# demo2.net
KiCad netlist of a schematic drawn in EAGLE
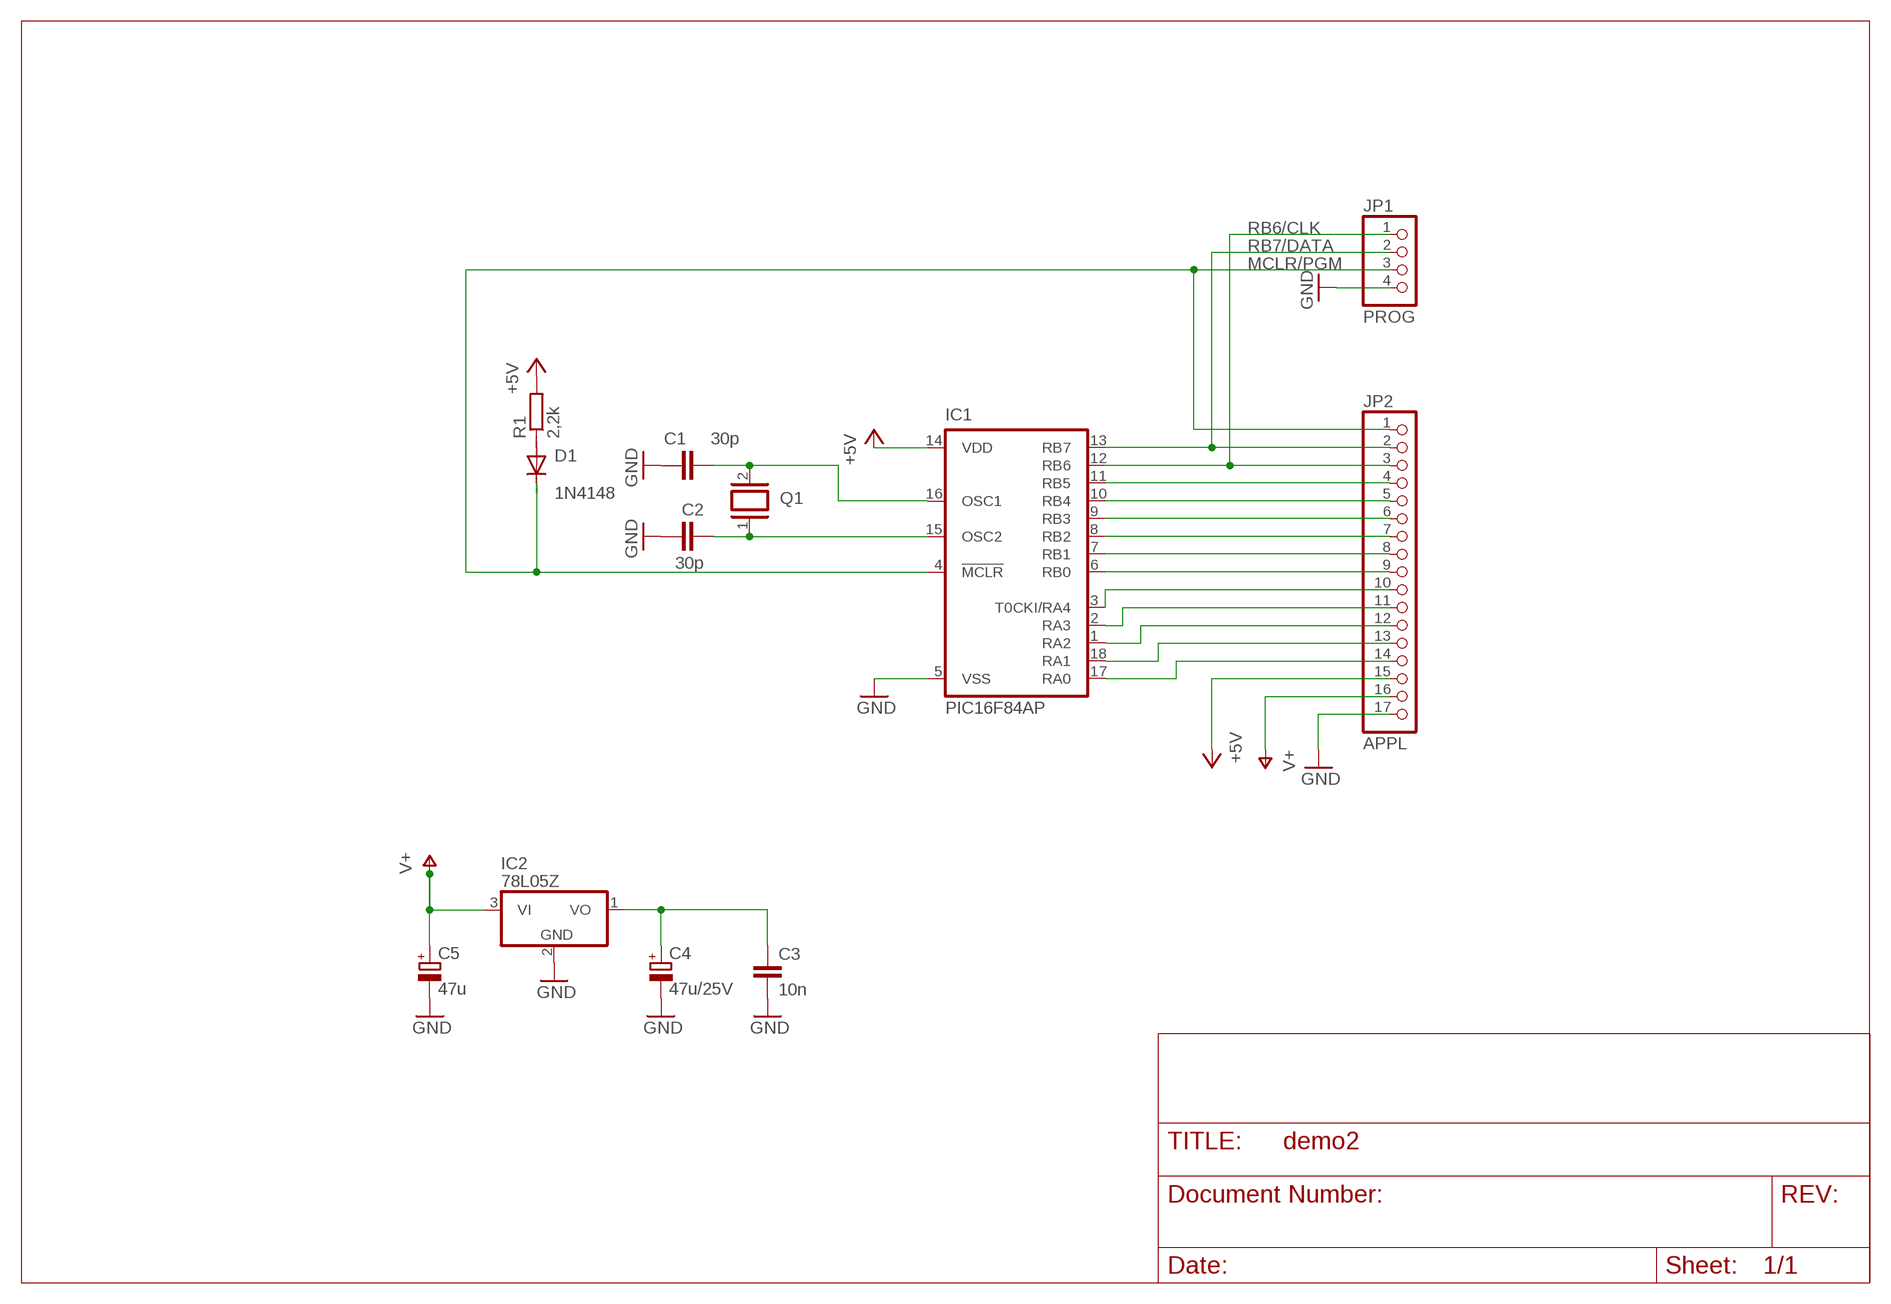
[diagram p0: schematic, sheet 1]

(export (version "E")
  (design (tool "Eeschema 10.0.6"))
  (components
    (comp (ref "C1")
      (value "30p")
      (footprint "eagle-import:C1206")
      (libsource (lib "eagle-import") (part "C-EUC1206"))
    )
    (comp (ref "C2")
      (value "30p")
      (footprint "eagle-import:C1206")
      (libsource (lib "eagle-import") (part "C-EUC1206"))
    )
    (comp (ref "C3")
      (value "10n")
      (footprint "eagle-import:C025-025X050")
      (libsource (lib "eagle-import") (part "C-EU025-025X050"))
    )
    (comp (ref "C4")
      (value "47u/25V")
      (footprint "eagle-import:TAP5-45")
      (libsource (lib "eagle-import") (part "CPOL-EUTAP5-45"))
    )
    (comp (ref "C5")
      (value "47u")
      (footprint "eagle-import:TAP5-45")
      (libsource (lib "eagle-import") (part "CPOL-EUTAP5-45"))
    )
    (comp (ref "D1")
      (value "1N4148")
      (footprint "eagle-import:DO35-10")
      (libsource (lib "eagle-import") (part "1N4148DO35-10"))
    )
    (comp (ref "IC1")
      (value "PIC16F84AP")
      (footprint "eagle-import:DIL18")
      (fields (field (name "MF") "MICROCHIP") (field (name "MPN") "PIC16F84A-04I/P"))
      (libsource (lib "eagle-import") (part "PIC16F8P4A"))
    )
    (comp (ref "IC2")
      (value "78L05Z")
      (footprint "eagle-import:TO92")
      (libsource (lib "eagle-import") (part "78ZL05"))
    )
    (comp (ref "JP1")
      (value "PROG")
      (footprint "eagle-import:1X04")
      (libsource (lib "eagle-import") (part "PINHD-1X4"))
    )
    (comp (ref "JP2")
      (value "APPL")
      (footprint "eagle-import:1X17")
      (libsource (lib "eagle-import") (part "PINHD-1X17"))
    )
    (comp (ref "Q1")
      (value "XTAL/S")
      (footprint "eagle-import:QS")
      (libsource (lib "eagle-import") (part "XTAL/S"))
    )
    (comp (ref "R1")
      (value "2,2k")
      (footprint "eagle-import:R1206")
      (libsource (lib "eagle-import") (part "R-EU_R1206"))
    )
  )
  (nets
    (net (code "1") (name "+5V") (class "Default")
      (node (ref "IC1") (pin "14") (pinfunction "VDD_14") (pintype "power_in"))
      (node (ref "JP2") (pin "15") (pinfunction "15_15") (pintype "passive"))
      (node (ref "R1") (pin "2") (pinfunction "2_2") (pintype "passive"))
    )
    (net (code "2") (name "/MCLR{slash}PGM") (class "Default")
      (node (ref "D1") (pin "C") (pinfunction "C_C") (pintype "passive"))
      (node (ref "IC1") (pin "4") (pinfunction "~{MCLR}_4") (pintype "input"))
      (node (ref "JP1") (pin "3") (pinfunction "3_3") (pintype "passive"))
      (node (ref "JP2") (pin "1") (pinfunction "1_1") (pintype "passive"))
    )
    (net (code "3") (name "/RB6{slash}CLK") (class "Default")
      (node (ref "IC1") (pin "12") (pinfunction "RB6_12") (pintype "bidirectional"))
      (node (ref "JP1") (pin "1") (pinfunction "1_1") (pintype "passive"))
      (node (ref "JP2") (pin "3") (pinfunction "3_3") (pintype "passive"))
    )
    (net (code "4") (name "/RB7{slash}DATA") (class "Default")
      (node (ref "IC1") (pin "13") (pinfunction "RB7_13") (pintype "bidirectional"))
      (node (ref "JP1") (pin "2") (pinfunction "2_2") (pintype "passive"))
      (node (ref "JP2") (pin "2") (pinfunction "2_2") (pintype "passive"))
    )
    (net (code "5") (name "GND") (class "Default")
      (node (ref "C1") (pin "1") (pinfunction "1_1") (pintype "passive"))
      (node (ref "C2") (pin "1") (pinfunction "1_1") (pintype "passive"))
      (node (ref "C3") (pin "2") (pinfunction "2_2") (pintype "passive"))
      (node (ref "C4") (pin "-") (pinfunction "-_-") (pintype "passive"))
      (node (ref "C5") (pin "-") (pinfunction "-_-") (pintype "passive"))
      (node (ref "IC1") (pin "5") (pinfunction "VSS_5") (pintype "power_in"))
      (node (ref "IC2") (pin "2") (pinfunction "GND_2") (pintype "passive"))
      (node (ref "JP1") (pin "4") (pinfunction "4_4") (pintype "passive"))
      (node (ref "JP2") (pin "17") (pinfunction "17_17") (pintype "passive"))
    )
    (net (code "6") (name "Net-(D1-PadA)") (class "Default")
      (node (ref "D1") (pin "A") (pinfunction "A_A") (pintype "passive"))
      (node (ref "R1") (pin "1") (pinfunction "1_1") (pintype "passive"))
    )
    (net (code "7") (name "Net-(IC1-OSC1)") (class "Default")
      (node (ref "C1") (pin "2") (pinfunction "2_2") (pintype "passive"))
      (node (ref "IC1") (pin "16") (pinfunction "OSC1_16") (pintype "input"))
      (node (ref "Q1") (pin "2") (pinfunction "2_2") (pintype "passive"))
    )
    (net (code "8") (name "Net-(IC1-OSC2)") (class "Default")
      (node (ref "C2") (pin "2") (pinfunction "2_2") (pintype "passive"))
      (node (ref "IC1") (pin "15") (pinfunction "OSC2_15") (pintype "output"))
      (node (ref "Q1") (pin "1") (pinfunction "1_1") (pintype "passive"))
    )
    (net (code "9") (name "Net-(IC1-RA0)") (class "Default")
      (node (ref "IC1") (pin "17") (pinfunction "RA0_17") (pintype "bidirectional"))
      (node (ref "JP2") (pin "14") (pinfunction "14_14") (pintype "passive"))
    )
    (net (code "10") (name "Net-(IC1-RA1)") (class "Default")
      (node (ref "IC1") (pin "18") (pinfunction "RA1_18") (pintype "bidirectional"))
      (node (ref "JP2") (pin "13") (pinfunction "13_13") (pintype "passive"))
    )
    (net (code "11") (name "Net-(IC1-RA2)") (class "Default")
      (node (ref "IC1") (pin "1") (pinfunction "RA2_1") (pintype "bidirectional"))
      (node (ref "JP2") (pin "12") (pinfunction "12_12") (pintype "passive"))
    )
    (net (code "12") (name "Net-(IC1-RA3)") (class "Default")
      (node (ref "IC1") (pin "2") (pinfunction "RA3_2") (pintype "bidirectional"))
      (node (ref "JP2") (pin "11") (pinfunction "11_11") (pintype "passive"))
    )
    (net (code "13") (name "Net-(IC1-RB0)") (class "Default")
      (node (ref "IC1") (pin "6") (pinfunction "RB0_6") (pintype "bidirectional"))
      (node (ref "JP2") (pin "9") (pinfunction "9_9") (pintype "passive"))
    )
    (net (code "14") (name "Net-(IC1-RB1)") (class "Default")
      (node (ref "IC1") (pin "7") (pinfunction "RB1_7") (pintype "bidirectional"))
      (node (ref "JP2") (pin "8") (pinfunction "8_8") (pintype "passive"))
    )
    (net (code "15") (name "Net-(IC1-RB2)") (class "Default")
      (node (ref "IC1") (pin "8") (pinfunction "RB2_8") (pintype "bidirectional"))
      (node (ref "JP2") (pin "7") (pinfunction "7_7") (pintype "passive"))
    )
    (net (code "16") (name "Net-(IC1-RB3)") (class "Default")
      (node (ref "IC1") (pin "9") (pinfunction "RB3_9") (pintype "bidirectional"))
      (node (ref "JP2") (pin "6") (pinfunction "6_6") (pintype "passive"))
    )
    (net (code "17") (name "Net-(IC1-RB4)") (class "Default")
      (node (ref "IC1") (pin "10") (pinfunction "RB4_10") (pintype "bidirectional"))
      (node (ref "JP2") (pin "5") (pinfunction "5_5") (pintype "passive"))
    )
    (net (code "18") (name "Net-(IC1-RB5)") (class "Default")
      (node (ref "IC1") (pin "11") (pinfunction "RB5_11") (pintype "bidirectional"))
      (node (ref "JP2") (pin "4") (pinfunction "4_4") (pintype "passive"))
    )
    (net (code "19") (name "Net-(IC1-T0CKI{slash}RA4)") (class "Default")
      (node (ref "IC1") (pin "3") (pinfunction "T0CKI/RA4_3") (pintype "bidirectional"))
      (node (ref "JP2") (pin "10") (pinfunction "10_10") (pintype "passive"))
    )
    (net (code "20") (name "Net-(IC2-VO)") (class "Default")
      (node (ref "C3") (pin "1") (pinfunction "1_1") (pintype "passive"))
      (node (ref "C4") (pin "+") (pinfunction "+_+") (pintype "passive"))
      (node (ref "IC2") (pin "1") (pinfunction "VO_1") (pintype "passive"))
    )
    (net (code "21") (name "V+") (class "Default")
      (node (ref "C5") (pin "+") (pinfunction "+_+") (pintype "passive"))
      (node (ref "IC2") (pin "3") (pinfunction "VI_3") (pintype "input"))
      (node (ref "JP2") (pin "16") (pinfunction "16_16") (pintype "passive"))
    )
  )
)
